# DM1097_BOOT_AUX_uSD.net
KiCad netlist of a schematic drawn in Altium Designer
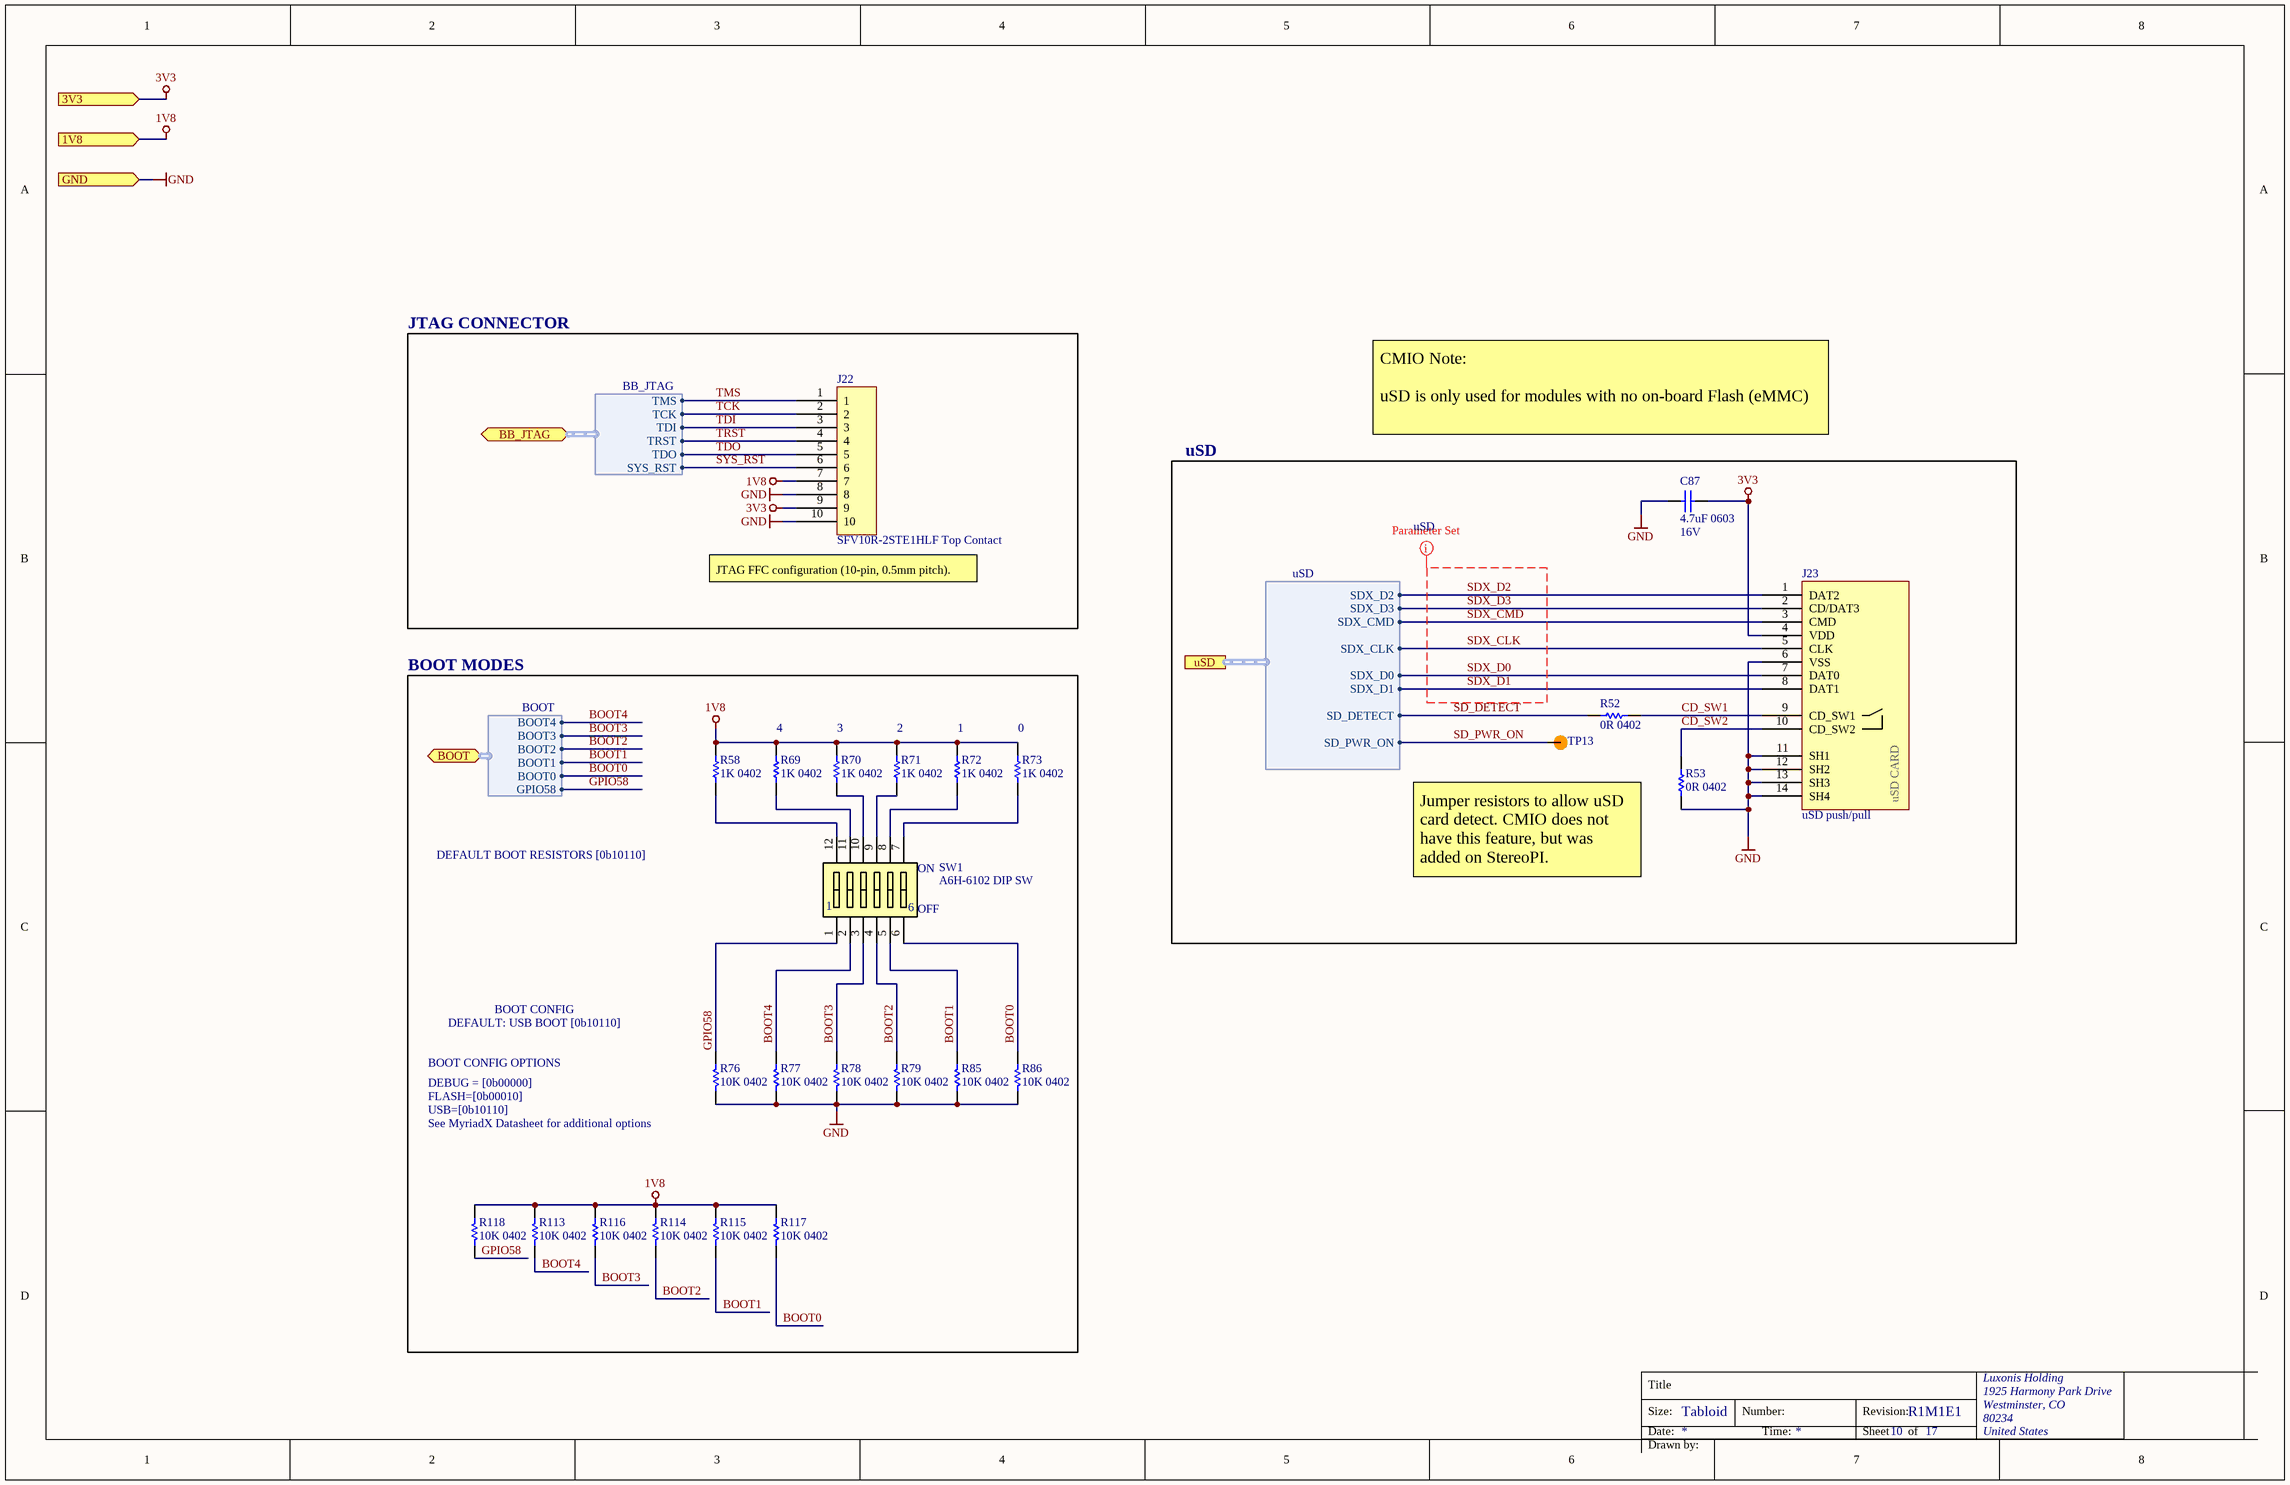
[diagram p0: DM1097_BOOT_AUX_uSD.SchDoc]

(export (version "E")
  (design (tool "Eeschema 10.0.6"))
  (components
    (comp (ref "C87")
      (value "4.7uF 0603")
      (footprint "CAP_Altium_Vault_Generic:CAPC0603(1608)100_N")
      (description "CAP CER 4.7UF 16V X5R 0603 10%")
      (fields (field (name "TOLERANCE") "10%") (field (name "VOLTAGE RATING") "16V"))
      (libsource (lib "LuxonisMaster") (part "GRM188R61C475KAAJD"))
    )
    (comp (ref "J22")
      (value "SFV10R-2STE1HLF Top Contact")
      (footprint "LuxonisMaster:SFV10R-2STE1HLF")
      (description "CONN FFC TOP 10POS 0.50MM R/A")
      (libsource (lib "LuxonisMaster") (part "SFV10R-2STE1HLF"))
    )
    (comp (ref "J23")
      (value "uSD push/pull")
      (footprint "LuxonisMaster:104031-0811")
      (description "CONN MICRO SD CARD PUSH-PULL R/A")
      (libsource (lib "LuxonisMaster") (part "104031-0811"))
    )
    (comp (ref "R52")
      (value "0R 0402")
      (footprint "RES_Altium_Vault_Generic:RESC0402(1005)_N")
      (description "RES SMD 0 OHM JUMPER 1/16W 0402")
      (fields (field (name "TOLERANCE") "5%"))
      (libsource (lib "LuxonisMaster") (part "CRCW04020000Z0ED"))
    )
    (comp (ref "R53")
      (value "0R 0402")
      (footprint "RES_Altium_Vault_Generic:RESC0402(1005)_N")
      (description "RES SMD 0 OHM JUMPER 1/16W 0402")
      (fields (field (name "TOLERANCE") "5%"))
      (libsource (lib "LuxonisMaster") (part "CRCW04020000Z0ED"))
    )
    (comp (ref "R58")
      (value "1K 0402")
      (footprint "RES_Altium_Vault_Generic:RESC0402(1005)_N")
      (fields (field (name "TOLERANCE") "1%"))
      (libsource (lib "LuxonisMaster") (part "RC0402FR-071KL"))
    )
    (comp (ref "R69")
      (value "1K 0402")
      (footprint "RES_Altium_Vault_Generic:RESC0402(1005)_N")
      (fields (field (name "TOLERANCE") "1%"))
      (libsource (lib "LuxonisMaster") (part "RC0402FR-071KL"))
    )
    (comp (ref "R70")
      (value "1K 0402")
      (footprint "RES_Altium_Vault_Generic:RESC0402(1005)_N")
      (fields (field (name "TOLERANCE") "1%"))
      (libsource (lib "LuxonisMaster") (part "RC0402FR-071KL"))
    )
    (comp (ref "R71")
      (value "1K 0402")
      (footprint "RES_Altium_Vault_Generic:RESC0402(1005)_N")
      (fields (field (name "TOLERANCE") "1%"))
      (libsource (lib "LuxonisMaster") (part "RC0402FR-071KL"))
    )
    (comp (ref "R72")
      (value "1K 0402")
      (footprint "RES_Altium_Vault_Generic:RESC0402(1005)_N")
      (fields (field (name "TOLERANCE") "1%"))
      (libsource (lib "LuxonisMaster") (part "RC0402FR-071KL"))
    )
    (comp (ref "R73")
      (value "1K 0402")
      (footprint "RES_Altium_Vault_Generic:RESC0402(1005)_N")
      (fields (field (name "TOLERANCE") "1%"))
      (libsource (lib "LuxonisMaster") (part "RC0402FR-071KL"))
    )
    (comp (ref "R76")
      (value "10K 0402")
      (footprint "RES_Altium_Vault_Generic:RESC0402(1005)_N")
      (fields (field (name "TOLERANCE") "1%"))
      (libsource (lib "LuxonisMaster") (part "RC0402FR-1310KL"))
    )
    (comp (ref "R77")
      (value "10K 0402")
      (footprint "RES_Altium_Vault_Generic:RESC0402(1005)_N")
      (fields (field (name "TOLERANCE") "1%"))
      (libsource (lib "LuxonisMaster") (part "RC0402FR-1310KL"))
    )
    (comp (ref "R78")
      (value "10K 0402")
      (footprint "RES_Altium_Vault_Generic:RESC0402(1005)_N")
      (fields (field (name "TOLERANCE") "1%"))
      (libsource (lib "LuxonisMaster") (part "RC0402FR-1310KL"))
    )
    (comp (ref "R79")
      (value "10K 0402")
      (footprint "RES_Altium_Vault_Generic:RESC0402(1005)_N")
      (fields (field (name "TOLERANCE") "1%"))
      (libsource (lib "LuxonisMaster") (part "RC0402FR-1310KL"))
    )
    (comp (ref "R85")
      (value "10K 0402")
      (footprint "RES_Altium_Vault_Generic:RESC0402(1005)_N")
      (fields (field (name "TOLERANCE") "1%"))
      (libsource (lib "LuxonisMaster") (part "RC0402FR-1310KL"))
    )
    (comp (ref "R86")
      (value "10K 0402")
      (footprint "RES_Altium_Vault_Generic:RESC0402(1005)_N")
      (fields (field (name "TOLERANCE") "1%"))
      (libsource (lib "LuxonisMaster") (part "RC0402FR-1310KL"))
    )
    (comp (ref "R113")
      (value "10K 0402")
      (footprint "RES_Altium_Vault_Generic:RESC0402(1005)_N")
      (fields (field (name "TOLERANCE") "1%"))
      (libsource (lib "LuxonisMaster") (part "RC0402FR-1310KL"))
    )
    (comp (ref "R114")
      (value "10K 0402")
      (footprint "RES_Altium_Vault_Generic:RESC0402(1005)_N")
      (fields (field (name "TOLERANCE") "1%"))
      (libsource (lib "LuxonisMaster") (part "RC0402FR-1310KL"))
    )
    (comp (ref "R115")
      (value "10K 0402")
      (footprint "RES_Altium_Vault_Generic:RESC0402(1005)_N")
      (fields (field (name "TOLERANCE") "1%"))
      (libsource (lib "LuxonisMaster") (part "RC0402FR-1310KL"))
    )
    (comp (ref "R116")
      (value "10K 0402")
      (footprint "RES_Altium_Vault_Generic:RESC0402(1005)_N")
      (fields (field (name "TOLERANCE") "1%"))
      (libsource (lib "LuxonisMaster") (part "RC0402FR-1310KL"))
    )
    (comp (ref "R117")
      (value "10K 0402")
      (footprint "RES_Altium_Vault_Generic:RESC0402(1005)_N")
      (fields (field (name "TOLERANCE") "1%"))
      (libsource (lib "LuxonisMaster") (part "RC0402FR-1310KL"))
    )
    (comp (ref "R118")
      (value "10K 0402")
      (footprint "RES_Altium_Vault_Generic:RESC0402(1005)_N")
      (fields (field (name "TOLERANCE") "1%"))
      (libsource (lib "LuxonisMaster") (part "RC0402FR-1310KL"))
    )
    (comp (ref "SW1")
      (value "A6H-6102 DIP SW")
      (footprint "LuxonisMaster:A6H-610x")
      (description "SWITCH SLIDE DIP SPST 25MA 24V (SEALED)")
      (libsource (lib "LuxonisMaster") (part "A6H-6102"))
    )
    (comp (ref "TP13")
      (value "TP100_200_NS")
      (footprint "LuxonisMaster:TP100_200_NS")
      (libsource (lib "LuxonisMaster") (part "TEST_POINT"))
    )
  )
  (nets
    (net (code "4") (name "/BOOT0") (class "Default")
      (node (ref "R117") (pin "2") (pinfunction "2_2") (pintype "passive"))
      (node (ref "R86") (pin "1") (pinfunction "1_1") (pintype "passive"))
      (node (ref "SW1") (pin "6") (pinfunction "6_6") (pintype "passive"))
    )
    (net (code "5") (name "/BOOT1") (class "Default")
      (node (ref "R115") (pin "2") (pinfunction "2_2") (pintype "passive"))
      (node (ref "R85") (pin "1") (pinfunction "1_1") (pintype "passive"))
      (node (ref "SW1") (pin "5") (pinfunction "5_5") (pintype "passive"))
    )
    (net (code "6") (name "/BOOT2") (class "Default")
      (node (ref "R114") (pin "2") (pinfunction "2_2") (pintype "passive"))
      (node (ref "R79") (pin "1") (pinfunction "1_1") (pintype "passive"))
      (node (ref "SW1") (pin "4") (pinfunction "4_4") (pintype "passive"))
    )
    (net (code "7") (name "/BOOT3") (class "Default")
      (node (ref "R116") (pin "2") (pinfunction "2_2") (pintype "passive"))
      (node (ref "R78") (pin "1") (pinfunction "1_1") (pintype "passive"))
      (node (ref "SW1") (pin "3") (pinfunction "3_3") (pintype "passive"))
    )
    (net (code "8") (name "/BOOT4") (class "Default")
      (node (ref "R113") (pin "2") (pinfunction "2_2") (pintype "passive"))
      (node (ref "R77") (pin "1") (pinfunction "1_1") (pintype "passive"))
      (node (ref "SW1") (pin "2") (pinfunction "2_2") (pintype "passive"))
    )
    (net (code "9") (name "/CD_SW1") (class "Default")
      (node (ref "J23") (pin "9") (pinfunction "CD_SW1_9") (pintype "passive"))
      (node (ref "R52") (pin "1") (pinfunction "1_1") (pintype "passive"))
    )
    (net (code "10") (name "/CD_SW2") (class "Default")
      (node (ref "J23") (pin "10") (pinfunction "CD_SW2_10") (pintype "passive"))
      (node (ref "R53") (pin "2") (pinfunction "2_2") (pintype "passive"))
    )
    (net (code "11") (name "/GPIO58") (class "Default")
      (node (ref "R118") (pin "2") (pinfunction "2_2") (pintype "passive"))
      (node (ref "R76") (pin "1") (pinfunction "1_1") (pintype "passive"))
      (node (ref "SW1") (pin "1") (pinfunction "1_1") (pintype "passive"))
    )
    (net (code "12") (name "/SDX_CLK") (class "Default")
      (node (ref "J23") (pin "5") (pinfunction "CLK_5") (pintype "passive"))
    )
    (net (code "13") (name "/SDX_CMD") (class "Default")
      (node (ref "J23") (pin "3") (pinfunction "CMD_3") (pintype "passive"))
    )
    (net (code "14") (name "/SDX_D0") (class "Default")
      (node (ref "J23") (pin "7") (pinfunction "DAT0_7") (pintype "passive"))
    )
    (net (code "15") (name "/SDX_D1") (class "Default")
      (node (ref "J23") (pin "8") (pinfunction "DAT1_8") (pintype "passive"))
    )
    (net (code "16") (name "/SDX_D2") (class "Default")
      (node (ref "J23") (pin "1") (pinfunction "DAT2_1") (pintype "passive"))
    )
    (net (code "17") (name "/SDX_D3") (class "Default")
      (node (ref "J23") (pin "2") (pinfunction "CD/DAT3_2") (pintype "passive"))
    )
    (net (code "18") (name "/SD_DETECT") (class "Default")
      (node (ref "R52") (pin "2") (pinfunction "2_2") (pintype "passive"))
    )
    (net (code "19") (name "/SD_PWR_ON") (class "Default") (node (ref "TP13") (pin "1") (pintype "passive")))
    (net (code "20") (name "/SYS_RST") (class "Default")
      (node (ref "J22") (pin "6") (pinfunction "6_6") (pintype "passive"))
    )
    (net (code "21") (name "/TCK") (class "Default")
      (node (ref "J22") (pin "2") (pinfunction "2_2") (pintype "passive"))
    )
    (net (code "22") (name "/TDI") (class "Default")
      (node (ref "J22") (pin "3") (pinfunction "3_3") (pintype "passive"))
    )
    (net (code "23") (name "/TDO") (class "Default")
      (node (ref "J22") (pin "5") (pinfunction "5_5") (pintype "passive"))
    )
    (net (code "24") (name "/TMS") (class "Default")
      (node (ref "J22") (pin "1") (pinfunction "1_1") (pintype "passive"))
    )
    (net (code "25") (name "/TRST") (class "Default")
      (node (ref "J22") (pin "4") (pinfunction "4_4") (pintype "passive"))
    )
    (net (code "29") (name "1V8") (class "Default")
      (node (ref "J22") (pin "7") (pinfunction "7_7") (pintype "passive"))
      (node (ref "R113") (pin "1") (pinfunction "1_1") (pintype "passive"))
      (node (ref "R114") (pin "1") (pinfunction "1_1") (pintype "passive"))
      (node (ref "R115") (pin "1") (pinfunction "1_1") (pintype "passive"))
      (node (ref "R116") (pin "1") (pinfunction "1_1") (pintype "passive"))
      (node (ref "R117") (pin "1") (pinfunction "1_1") (pintype "passive"))
      (node (ref "R118") (pin "1") (pinfunction "1_1") (pintype "passive"))
      (node (ref "R58") (pin "2") (pinfunction "2_2") (pintype "passive"))
      (node (ref "R69") (pin "2") (pinfunction "2_2") (pintype "passive"))
      (node (ref "R70") (pin "2") (pinfunction "2_2") (pintype "passive"))
      (node (ref "R71") (pin "2") (pinfunction "2_2") (pintype "passive"))
      (node (ref "R72") (pin "2") (pinfunction "2_2") (pintype "passive"))
      (node (ref "R73") (pin "2") (pinfunction "2_2") (pintype "passive"))
    )
    (net (code "30") (name "3V3") (class "Default")
      (node (ref "C87") (pin "2") (pinfunction "2_2") (pintype "passive"))
      (node (ref "J22") (pin "9") (pinfunction "9_9") (pintype "passive"))
      (node (ref "J23") (pin "4") (pinfunction "VDD_4") (pintype "passive"))
    )
    (net (code "31") (name "GND") (class "Default")
      (node (ref "C87") (pin "1") (pinfunction "1_1") (pintype "passive"))
      (node (ref "J22") (pin "10") (pinfunction "10_10") (pintype "passive"))
      (node (ref "J22") (pin "8") (pinfunction "8_8") (pintype "passive"))
      (node (ref "J23") (pin "11") (pinfunction "SH1_11") (pintype "passive"))
      (node (ref "J23") (pin "12") (pinfunction "SH2_12") (pintype "passive"))
      (node (ref "J23") (pin "13") (pinfunction "SH3_13") (pintype "passive"))
      (node (ref "J23") (pin "14") (pinfunction "SH4_14") (pintype "passive"))
      (node (ref "J23") (pin "6") (pinfunction "VSS_6") (pintype "passive"))
      (node (ref "R53") (pin "1") (pinfunction "1_1") (pintype "passive"))
      (node (ref "R76") (pin "2") (pinfunction "2_2") (pintype "passive"))
      (node (ref "R77") (pin "2") (pinfunction "2_2") (pintype "passive"))
      (node (ref "R78") (pin "2") (pinfunction "2_2") (pintype "passive"))
      (node (ref "R79") (pin "2") (pinfunction "2_2") (pintype "passive"))
      (node (ref "R85") (pin "2") (pinfunction "2_2") (pintype "passive"))
      (node (ref "R86") (pin "2") (pinfunction "2_2") (pintype "passive"))
    )
    (net (code "32") (name "Net-(R58-Pad1)") (class "Default")
      (node (ref "R58") (pin "1") (pinfunction "1_1") (pintype "passive"))
      (node (ref "SW1") (pin "12") (pinfunction "12_12") (pintype "passive"))
    )
    (net (code "33") (name "Net-(R69-Pad1)") (class "Default")
      (node (ref "R69") (pin "1") (pinfunction "1_1") (pintype "passive"))
      (node (ref "SW1") (pin "11") (pinfunction "11_11") (pintype "passive"))
    )
    (net (code "34") (name "Net-(R70-Pad1)") (class "Default")
      (node (ref "R70") (pin "1") (pinfunction "1_1") (pintype "passive"))
      (node (ref "SW1") (pin "10") (pinfunction "10_10") (pintype "passive"))
    )
    (net (code "35") (name "Net-(R71-Pad1)") (class "Default")
      (node (ref "R71") (pin "1") (pinfunction "1_1") (pintype "passive"))
      (node (ref "SW1") (pin "9") (pinfunction "9_9") (pintype "passive"))
    )
    (net (code "36") (name "Net-(R72-Pad1)") (class "Default")
      (node (ref "R72") (pin "1") (pinfunction "1_1") (pintype "passive"))
      (node (ref "SW1") (pin "8") (pinfunction "8_8") (pintype "passive"))
    )
    (net (code "37") (name "Net-(R73-Pad1)") (class "Default")
      (node (ref "R73") (pin "1") (pinfunction "1_1") (pintype "passive"))
      (node (ref "SW1") (pin "7") (pinfunction "7_7") (pintype "passive"))
    )
  )
)
